# USB_PD.net
KiCad netlist of a schematic drawn in Altium Designer
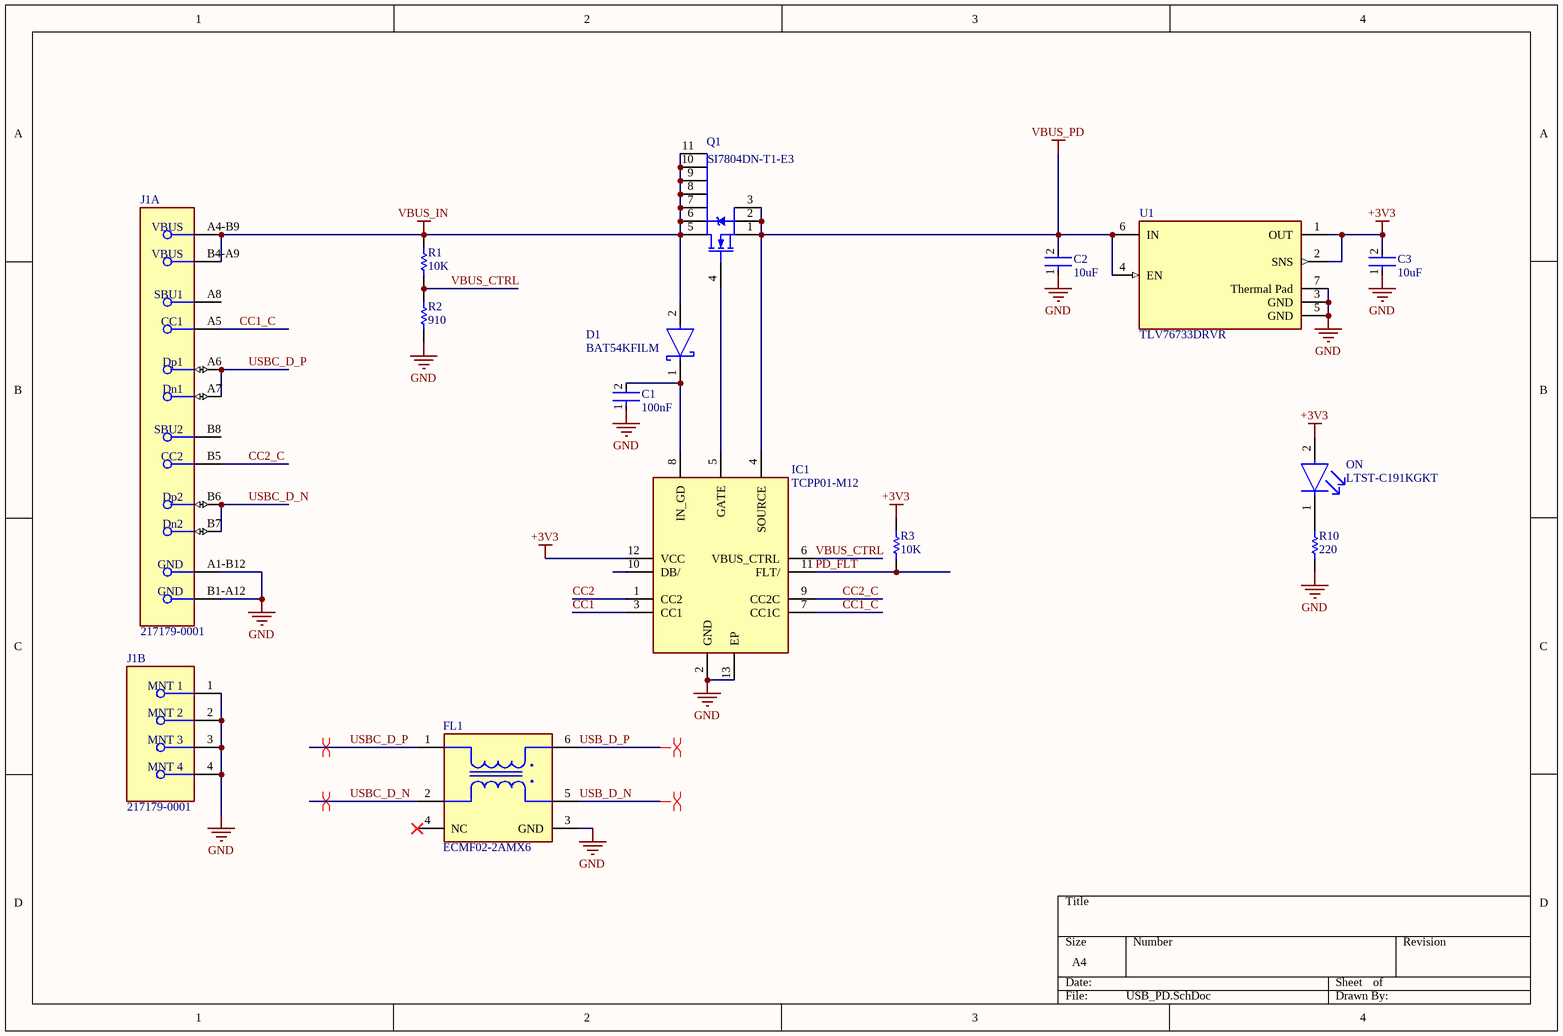
[diagram p0: USB_PD.SchDoc]

(export (version "E")
  (design (tool "Eeschema 10.0.6"))
  (components
    (comp (ref "C1")
      (value "C1005X7R1H104K050BB")
      (footprint "FP-C1005-050-0_05-IPC_C")
      (description "Multilayer Ceramic Capacitors 100nF ±10% 50V X7R SMD 0402")
      (fields
        (field (name "VOLTAGE") "50V")
        (field (name "CAPACITANCE") "100nF")
        (field (name "TOLERANCE") "10%")
      )
      (libsource (lib "Altium Content Vault") (part "b4654b650e69147ec39a6b967a45e02"))
    )
    (comp (ref "C2")
      (value "C1608X5R1E106M080AC")
      (footprint "FP-C1608-080-IPC_A")
      (description "CAP CER 10UF 25V X5R 0603")
      (fields (field (name "TOLERANCE") "20%") (field (name "CAPACITANCE") "10uF"))
      (libsource (lib "Altium Content Vault") (part "11868f565c42a9108669ba33697ecf6"))
    )
    (comp (ref "C3")
      (value "C1608X5R1E106M080AC")
      (footprint "FP-C1608-080-IPC_A")
      (description "CAP CER 10UF 25V X5R 0603")
      (fields (field (name "TOLERANCE") "20%") (field (name "CAPACITANCE") "10uF"))
      (libsource (lib "Altium Content Vault") (part "11868f565c42a9108669ba33697ecf6"))
    )
    (comp (ref "D1")
      (value "BAT54KFILM")
      (footprint "FP-SOD-523-MFG")
      (description "DIODE SCHOTTKY 40V 300MA SOD523")
      (fields
        (field (name "OCTOPART") "https://octopart.com/bat54kfilm-stmicroelectronics-39618022")
        (field (name "MANUFACTURER") "STMicroelectronics")
      )
      (libsource (lib "Altium Content Vault") (part "1d6ec82d83fb6aee721767c19dac4b9"))
    )
    (comp (ref "FL1")
      (value "ECMF02-2AMX6")
      (footprint "FP-QFN-6L-MFG")
      (description "CMC 200MA 2LN SMD ESD")
      (fields
        (field (name "MANUFACTURER") "STMicroelectronics")
        (field (name "OCTOPART") "https://octopart.com/ecmf02-2amx6-stmicroelectronics-44353078")
      )
      (libsource (lib "Altium Content Vault") (part "8feffc7f24acfb857157da90e949b57"))
    )
    (comp (ref "IC1")
      (value "TCPP01-M12")
      (footprint "SamacSys:QFN50P300X300X100-13N-D")
      (description "Integrated Circuit")
      (fields (field (name "MOUSER PART NUMBER") "511-TCPP01-M12"))
      (libsource (lib "SamacSys") (part "TCPP01-M12"))
    )
    (comp (ref "J1")
      (value "217179-0001")
      (footprint "FP-2171790001-MFG")
      (description "CONN RCP USB2.0 TYP C 24P SMD RA")
      (libsource (lib "Altium Content Vault") (part "8b86497a633d14b3f74642136fc0ce6"))
    )
    (comp (ref "ON")
      (value "LTST-C191KGKT")
      (footprint "FP-LTST-C191KGKT-MFG")
      (libsource (lib "Altium Content Vault") (part "8706943c75ba83719d021d2fdc84c58"))
    )
    (comp (ref "Q1")
      (value "SI7804DN-T1-E3")
      (footprint "SamacSys:SIS862DNT1GE3")
      (description "MOSFET (N-Channel)")
      (fields (field (name "MOUSER PART NUMBER") "781-SI7804DN-T1-E3"))
      (libsource (lib "SamacSys") (part "SI7804DN-T1-E3"))
    )
    (comp (ref "R1")
      (value "ERJ-2GEJ103X")
      (footprint "RESC1005X40X25ML05T05")
      (fields (field (name "MANUFACTURER") "Panasonic") (field (name "RESISTANCE") "10K"))
      (libsource (lib "Altium Content Vault") (part "RES"))
    )
    (comp (ref "R2")
      (value "ERJ-2GEJ911X")
      (footprint "RESC1005X40X25ML05T05")
      (fields (field (name "MANUFACTURER") "Panasonic") (field (name "ERJ-2GEJ103X") "910"))
      (libsource (lib "Altium Content Vault") (part "RES"))
    )
    (comp (ref "R3")
      (value "ERJ-2GEJ103X")
      (footprint "RESC1005X40X25ML05T05")
      (fields (field (name "MANUFACTURER") "Panasonic") (field (name "RESISTANCE") "10K"))
      (libsource (lib "Altium Content Vault") (part "RES"))
    )
    (comp (ref "R10")
      (value "ERJ2RKF2200X")
      (footprint "RESC1005X40X25LL05T05")
      (fields (field (name "MANUFACTURER") "Panasonic") (field (name "RESISTANCE") "220"))
      (libsource (lib "Altium Content Vault") (part "RES"))
    )
    (comp (ref "U1")
      (value "TLV76733DRVR")
      (footprint "FP-DRV0006A-IPC_C")
      (description "VOLTAGE COMPARATOR")
      (libsource (lib "Altium Content Vault") (part "527f072e48108a7b9f646086bfc5874"))
    )
  )
  (nets
    (net (code "1") (name "+3V3") (class "Default")
      (node (ref "C3") (pin "2") (pinfunction "2_2") (pintype "passive"))
      (node (ref "IC1") (pin "12") (pinfunction "VCC_12") (pintype "passive"))
      (node (ref "ON") (pin "2") (pinfunction "A_2") (pintype "passive"))
      (node (ref "R3") (pin "2") (pinfunction "2_2") (pintype "passive"))
      (node (ref "U1") (pin "1") (pinfunction "OUT_1") (pintype "passive"))
      (node (ref "U1") (pin "2") (pinfunction "SNS_2") (pintype "output"))
    )
    (net (code "2") (name "/CC1") (class "Default")
      (node (ref "IC1") (pin "3") (pinfunction "CC1_3") (pintype "passive"))
    )
    (net (code "3") (name "/CC1_C") (class "Default")
      (node (ref "IC1") (pin "7") (pinfunction "CC1C_7") (pintype "passive"))
      (node (ref "J1") (pin "A5") (pinfunction "CC1_A5") (pintype "passive"))
    )
    (net (code "4") (name "/CC2") (class "Default")
      (node (ref "IC1") (pin "1") (pinfunction "CC2_1") (pintype "passive"))
    )
    (net (code "5") (name "/CC2_C") (class "Default")
      (node (ref "IC1") (pin "9") (pinfunction "CC2C_9") (pintype "passive"))
      (node (ref "J1") (pin "B5") (pinfunction "CC2_B5") (pintype "passive"))
    )
    (net (code "6") (name "/PD_~{FLT}") (class "Default")
      (node (ref "IC1") (pin "11") (pinfunction "FLT/_11") (pintype "passive"))
      (node (ref "R3") (pin "1") (pinfunction "1_1") (pintype "passive"))
    )
    (net (code "7") (name "/USBC_D_N") (class "Default")
      (node (ref "FL1") (pin "2") (pinfunction "D-_2") (pintype "passive"))
      (node (ref "J1") (pin "B6") (pinfunction "Dp2_B6") (pintype "bidirectional"))
      (node (ref "J1") (pin "B7") (pinfunction "Dn2_B7") (pintype "bidirectional"))
    )
    (net (code "8") (name "/USBC_D_P") (class "Default")
      (node (ref "FL1") (pin "1") (pinfunction "D+_1") (pintype "passive"))
      (node (ref "J1") (pin "A6") (pinfunction "Dp1_A6") (pintype "bidirectional"))
      (node (ref "J1") (pin "A7") (pinfunction "Dn1_A7") (pintype "bidirectional"))
    )
    (net (code "9") (name "/USB_D_N") (class "Default")
      (node (ref "FL1") (pin "5") (pinfunction "D-_5") (pintype "passive"))
    )
    (net (code "10") (name "/USB_D_P") (class "Default")
      (node (ref "FL1") (pin "6") (pinfunction "D+_6") (pintype "passive"))
    )
    (net (code "11") (name "/VBUS_CTRL") (class "Default")
      (node (ref "IC1") (pin "6") (pinfunction "VBUS_CTRL_6") (pintype "passive"))
      (node (ref "R1") (pin "1") (pinfunction "1_1") (pintype "passive"))
      (node (ref "R2") (pin "2") (pinfunction "2_2") (pintype "passive"))
    )
    (net (code "12") (name "GND") (class "Default")
      (node (ref "C1") (pin "1") (pinfunction "1_1") (pintype "passive"))
      (node (ref "C2") (pin "1") (pinfunction "1_1") (pintype "passive"))
      (node (ref "C3") (pin "1") (pinfunction "1_1") (pintype "passive"))
      (node (ref "FL1") (pin "3") (pinfunction "GND_3") (pintype "power_in"))
      (node (ref "IC1") (pin "13") (pinfunction "EP_13") (pintype "passive"))
      (node (ref "IC1") (pin "2") (pinfunction "GND_2") (pintype "passive"))
      (node (ref "J1") (pin "1") (pinfunction "MNT_1_1") (pintype "passive"))
      (node (ref "J1") (pin "2") (pinfunction "MNT_2_2") (pintype "passive"))
      (node (ref "J1") (pin "3") (pinfunction "MNT_3_3") (pintype "power_in"))
      (node (ref "J1") (pin "4") (pinfunction "MNT_4_4") (pintype "power_in"))
      (node (ref "J1") (pin "A1-B12") (pinfunction "GND_A1-B12") (pintype "power_in"))
      (node (ref "J1") (pin "B1-A12") (pinfunction "GND_B1-A12") (pintype "power_in"))
      (node (ref "R10") (pin "2") (pinfunction "2_2") (pintype "passive"))
      (node (ref "R2") (pin "1") (pinfunction "1_1") (pintype "passive"))
      (node (ref "U1") (pin "3") (pinfunction "GND_3") (pintype "power_in"))
      (node (ref "U1") (pin "5") (pinfunction "GND_5") (pintype "power_in"))
      (node (ref "U1") (pin "7") (pinfunction "Thermal_Pad_7") (pintype "passive"))
    )
    (net (code "13") (name "Net-(D1-C)") (class "Default")
      (node (ref "C1") (pin "2") (pinfunction "2_2") (pintype "passive"))
      (node (ref "D1") (pin "1") (pinfunction "C_1") (pintype "passive"))
      (node (ref "IC1") (pin "8") (pinfunction "IN_GD_8") (pintype "passive"))
    )
    (net (code "14") (name "Net-(IC1-GATE)") (class "Default")
      (node (ref "IC1") (pin "5") (pinfunction "GATE_5") (pintype "passive"))
      (node (ref "Q1") (pin "4") (pinfunction "G_4") (pintype "passive"))
    )
    (net (code "15") (name "Net-(ON-C)") (class "Default")
      (node (ref "ON") (pin "1") (pinfunction "C_1") (pintype "passive"))
      (node (ref "R10") (pin "1") (pinfunction "1_1") (pintype "passive"))
    )
    (net (code "16") (name "VBUS_IN") (class "Default")
      (node (ref "D1") (pin "2") (pinfunction "A_2") (pintype "passive"))
      (node (ref "J1") (pin "A4-B9") (pinfunction "VBUS_A4-B9") (pintype "power_in"))
      (node (ref "J1") (pin "B4-A9") (pinfunction "VBUS_B4-A9") (pintype "power_in"))
      (node (ref "Q1") (pin "10") (pinfunction "D_6_10") (pintype "passive"))
      (node (ref "Q1") (pin "11") (pinfunction "D_7_11") (pintype "passive"))
      (node (ref "Q1") (pin "5") (pinfunction "D_1_5") (pintype "passive"))
      (node (ref "Q1") (pin "6") (pinfunction "D_2_6") (pintype "passive"))
      (node (ref "Q1") (pin "7") (pinfunction "D_3_7") (pintype "passive"))
      (node (ref "Q1") (pin "8") (pinfunction "D_4_8") (pintype "passive"))
      (node (ref "Q1") (pin "9") (pinfunction "D_5_9") (pintype "passive"))
      (node (ref "R1") (pin "2") (pinfunction "2_2") (pintype "passive"))
    )
    (net (code "17") (name "VBUS_PD") (class "Default")
      (node (ref "C2") (pin "2") (pinfunction "2_2") (pintype "passive"))
      (node (ref "IC1") (pin "4") (pinfunction "SOURCE_4") (pintype "passive"))
      (node (ref "Q1") (pin "1") (pinfunction "S_1_1") (pintype "passive"))
      (node (ref "Q1") (pin "2") (pinfunction "S_2_2") (pintype "passive"))
      (node (ref "Q1") (pin "3") (pinfunction "S_3_3") (pintype "passive"))
      (node (ref "U1") (pin "4") (pinfunction "EN_4") (pintype "input"))
      (node (ref "U1") (pin "6") (pinfunction "IN_6") (pintype "power_in"))
    )
    (net (code "18") (name "unconnected-(FL1-NC-Pad4)") (class "Default")
      (node (ref "FL1") (pin "4") (pinfunction "NC_4") (pintype "passive+no_connect"))
    )
    (net (code "19") (name "unconnected-(IC1-DB{slash}-Pad10)") (class "Default")
      (node (ref "IC1") (pin "10") (pinfunction "DB/_10") (pintype "passive"))
    )
    (net (code "20") (name "unconnected-(J1A-SBU1-PadA8)") (class "Default")
      (node (ref "J1") (pin "A8") (pinfunction "SBU1_A8") (pintype "passive"))
    )
    (net (code "21") (name "unconnected-(J1A-SBU2-PadB8)") (class "Default")
      (node (ref "J1") (pin "B8") (pinfunction "SBU2_B8") (pintype "passive"))
    )
  )
)
